# main.net
KiCad netlist of a schematic drawn in EAGLE
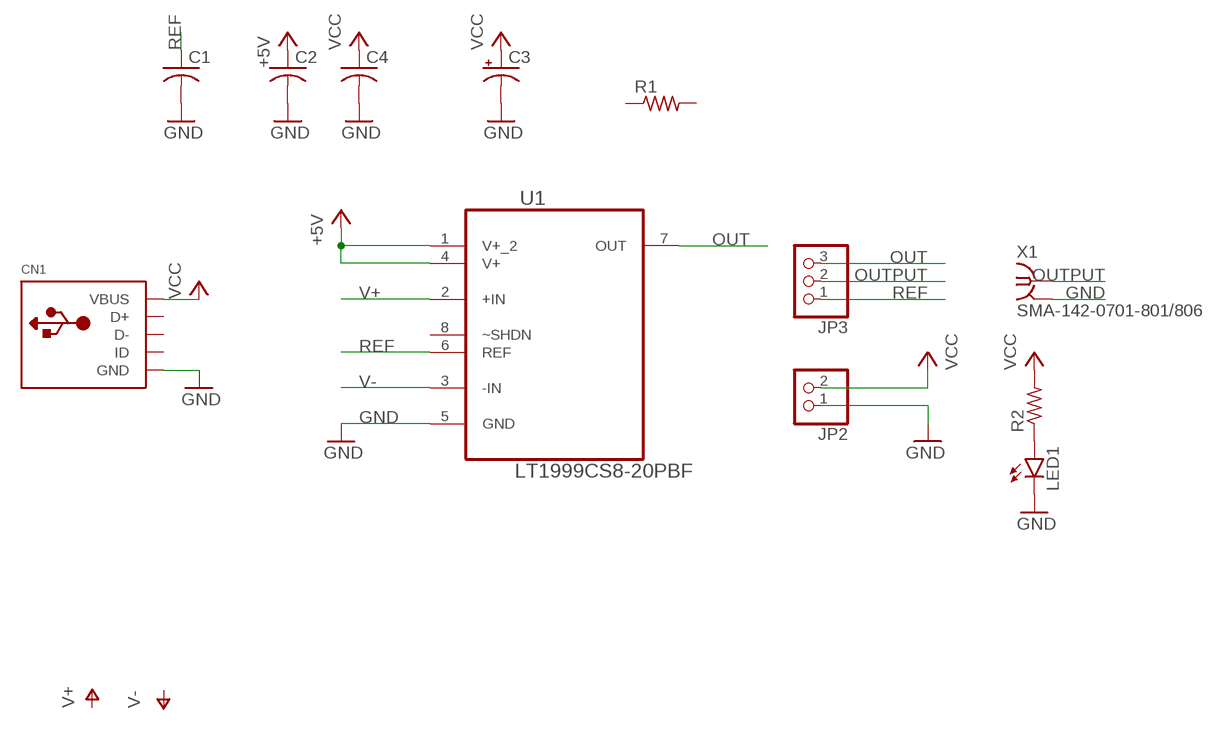
[diagram p0: schematic, sheet 1]

(export (version "E")
  (design (tool "Eeschema 10.0.6"))
  (components
    (comp (ref "C1")
      (value "C-US050-030X075")
      (footprint "eagle-import:C050-030X075")
      (libsource (lib "eagle-import") (part "C-US050-030X075"))
    )
    (comp (ref "C2")
      (value "C-US050-030X075")
      (footprint "eagle-import:C050-030X075")
      (libsource (lib "eagle-import") (part "C-US050-030X075"))
    )
    (comp (ref "C3")
      (value "CPOL-USE2-5")
      (footprint "eagle-import:E2-5")
      (libsource (lib "eagle-import") (part "CPOL-USE2-5"))
    )
    (comp (ref "C4")
      (value "C-US050-030X075")
      (footprint "eagle-import:C050-030X075")
      (libsource (lib "eagle-import") (part "C-US050-030X075"))
    )
    (comp (ref "CN1")
      (value "USBMINIB")
      (footprint "eagle-import:USB-MINIB")
      (libsource (lib "eagle-import") (part "USBMINIB"))
    )
    (comp (ref "JP2")
      (value "PINHD-1X2")
      (footprint "eagle-import:1X02")
      (libsource (lib "eagle-import") (part "PINHD-1X2"))
    )
    (comp (ref "JP3")
      (value "PINHD-1X3")
      (footprint "eagle-import:1X03")
      (libsource (lib "eagle-import") (part "PINHD-1X3"))
    )
    (comp (ref "LED1")
      (value "LEDCHIP-LED0603")
      (footprint "eagle-import:CHIP-LED0603")
      (libsource (lib "eagle-import") (part "LEDCHIP-LED0603"))
    )
    (comp (ref "R1")
      (value "R-US_0204/7")
      (footprint "eagle-import:0204_7")
      (libsource (lib "eagle-import") (part "R-US_0204/7"))
    )
    (comp (ref "R2")
      (value "R-US_R0603")
      (footprint "eagle-import:R0603")
      (libsource (lib "eagle-import") (part "R-US_R0603"))
    )
    (comp (ref "U1")
      (value "LT1999CS8-20PBF")
      (footprint "eagle-import:SOIC127P600X175-8N")
      (fields (field (name "MPN") "LT1999CS8-20#PBF"))
      (libsource (lib "eagle-import") (part "LT1999CS8-20PBF"))
    )
    (comp (ref "X1")
      (value "SMA-142-0701-801/806")
      (footprint "eagle-import:J502-ND-142-0701-801_806")
      (fields (field (name "MF") "JOHNSON COMPONENTS") (field (name "MPN") "142-0701-801"))
      (libsource (lib "eagle-import") (part "SMA-142-0701-801/806"))
    )
  )
  (nets
    (net (code "1") (name "+5V") (class "Default")
      (node (ref "C2") (pin "1") (pinfunction "1_1") (pintype "passive"))
      (node (ref "U1") (pin "1") (pinfunction "V+_2_1") (pintype "power_in"))
      (node (ref "U1") (pin "4") (pinfunction "V+_4") (pintype "power_in"))
    )
    (net (code "2") (name "/OUT") (class "Default")
      (node (ref "JP3") (pin "3") (pinfunction "3_3") (pintype "passive"))
      (node (ref "U1") (pin "7") (pinfunction "OUT_7") (pintype "output"))
    )
    (net (code "3") (name "/OUTPUT") (class "Default")
      (node (ref "JP3") (pin "2") (pinfunction "2_2") (pintype "passive"))
      (node (ref "X1") (pin "1") (pinfunction "1_1") (pintype "passive"))
    )
    (net (code "4") (name "/REF") (class "Default")
      (node (ref "C1") (pin "1") (pinfunction "1_1") (pintype "passive"))
      (node (ref "JP3") (pin "1") (pinfunction "1_1") (pintype "passive"))
      (node (ref "U1") (pin "6") (pinfunction "REF_6") (pintype "input"))
    )
    (net (code "5") (name "GND") (class "Default")
      (node (ref "C1") (pin "2") (pinfunction "2_2") (pintype "passive"))
      (node (ref "C2") (pin "2") (pinfunction "2_2") (pintype "passive"))
      (node (ref "C3") (pin "-") (pinfunction "-_-") (pintype "passive"))
      (node (ref "C4") (pin "2") (pinfunction "2_2") (pintype "passive"))
      (node (ref "CN1") (pin "GND") (pinfunction "GND_GND") (pintype "power_in"))
      (node (ref "JP2") (pin "1") (pinfunction "1_1") (pintype "passive"))
      (node (ref "LED1") (pin "C") (pinfunction "C_C") (pintype "passive"))
      (node (ref "U1") (pin "5") (pinfunction "GND_5") (pintype "passive"))
      (node (ref "X1") (pin "G@1") (pinfunction "2_G@1") (pintype "passive"))
      (node (ref "X1") (pin "G@2") (pinfunction "2_G@2") (pintype "passive"))
      (node (ref "X1") (pin "G@3") (pinfunction "2_G@3") (pintype "passive"))
      (node (ref "X1") (pin "G@4") (pinfunction "2_G@4") (pintype "passive"))
    )
    (net (code "6") (name "Net-(LED1-PadA)") (class "Default")
      (node (ref "LED1") (pin "A") (pinfunction "A_A") (pintype "passive"))
      (node (ref "R2") (pin "1") (pinfunction "1_1") (pintype "passive"))
    )
    (net (code "7") (name "V+") (class "Default")
      (node (ref "U1") (pin "2") (pinfunction "+IN_2") (pintype "input"))
    )
    (net (code "8") (name "V-") (class "Default")
      (node (ref "U1") (pin "3") (pinfunction "-IN_3") (pintype "input"))
    )
    (net (code "9") (name "VCC") (class "Default")
      (node (ref "C3") (pin "+") (pinfunction "+_+") (pintype "passive"))
      (node (ref "C4") (pin "1") (pinfunction "1_1") (pintype "passive"))
      (node (ref "CN1") (pin "VBUS") (pinfunction "VBUS_VBUS") (pintype "power_in"))
      (node (ref "JP2") (pin "2") (pinfunction "2_2") (pintype "passive"))
      (node (ref "R2") (pin "2") (pinfunction "2_2") (pintype "passive"))
    )
    (net (code "10") (name "unconnected-(CN1-PadD+)") (class "Default")
      (node (ref "CN1") (pin "D+") (pinfunction "D+_D+") (pintype "bidirectional"))
    )
    (net (code "11") (name "unconnected-(CN1-PadD-)") (class "Default")
      (node (ref "CN1") (pin "D-") (pinfunction "D-_D-") (pintype "bidirectional"))
    )
    (net (code "12") (name "unconnected-(CN1-PadID)") (class "Default")
      (node (ref "CN1") (pin "ID") (pinfunction "ID_ID") (pintype "bidirectional"))
    )
    (net (code "13") (name "unconnected-(R1-Pad1)") (class "Default")
      (node (ref "R1") (pin "1") (pinfunction "1_1") (pintype "passive"))
    )
    (net (code "14") (name "unconnected-(R1-Pad2)") (class "Default")
      (node (ref "R1") (pin "2") (pinfunction "2_2") (pintype "passive"))
    )
    (net (code "15") (name "unconnected-(U1-~{SHDN}-Pad8)") (class "Default")
      (node (ref "U1") (pin "8") (pinfunction "~{SHDN}_8") (pintype "input"))
    )
  )
)
